# GBZLNDShield.net
KiCad netlist of a schematic drawn in EAGLE
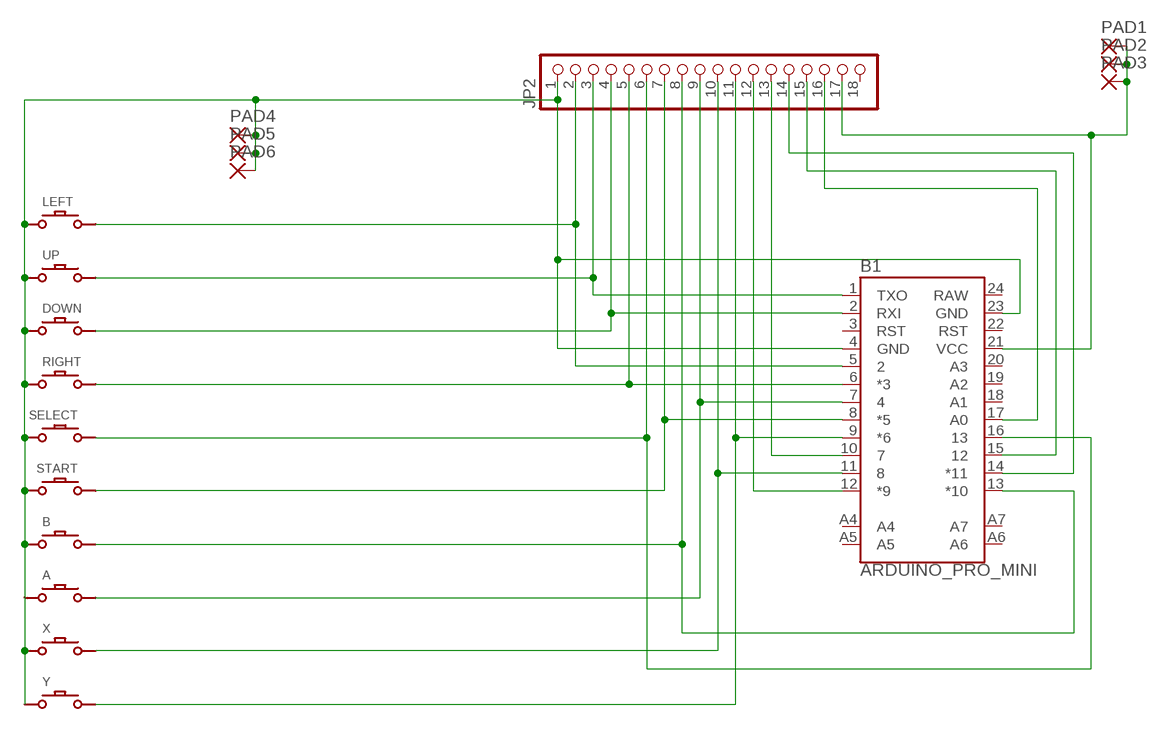
[diagram p0: schematic, sheet 1]

(export (version "E")
  (design (tool "Eeschema 10.0.6"))
  (components
    (comp (ref "A")
      (value "DMG-BTN")
      (footprint "eagle-import:DMG-BTN")
      (libsource (lib "eagle-import") (part "DMG-BTNREGULAR"))
    )
    (comp (ref "B")
      (value "DMG-BTN")
      (footprint "eagle-import:DMG-BTN")
      (libsource (lib "eagle-import") (part "DMG-BTNREGULAR"))
    )
    (comp (ref "B1")
      (value "ARDUINO_PRO_MINI")
      (footprint "eagle-import:ARDUINO_PRO_MINI")
      (libsource (lib "eagle-import") (part "ARDUINO_PRO_MINI"))
    )
    (comp (ref "DOWN")
      (value "DMG-BTN")
      (footprint "eagle-import:DMG-BTN")
      (libsource (lib "eagle-import") (part "DMG-BTNREGULAR"))
    )
    (comp (ref "JP2")
      (value "PINHD-1X18-BIG")
      (footprint "eagle-import:1X18-BIG")
      (libsource (lib "eagle-import") (part "PINHD-1X18-BIG"))
    )
    (comp (ref "LEFT")
      (value "DMG-BTN")
      (footprint "eagle-import:DMG-BTN")
      (libsource (lib "eagle-import") (part "DMG-BTNREGULAR"))
    )
    (comp (ref "PAD1")
      (value "SMD5")
      (footprint "eagle-import:SMD2,54-5,08")
      (libsource (lib "eagle-import") (part "SMD5"))
    )
    (comp (ref "PAD2")
      (value "SMD5")
      (footprint "eagle-import:SMD2,54-5,08")
      (libsource (lib "eagle-import") (part "SMD5"))
    )
    (comp (ref "PAD3")
      (value "SMD5")
      (footprint "eagle-import:SMD2,54-5,08")
      (libsource (lib "eagle-import") (part "SMD5"))
    )
    (comp (ref "PAD4")
      (value "SMD5")
      (footprint "eagle-import:SMD2,54-5,08")
      (libsource (lib "eagle-import") (part "SMD5"))
    )
    (comp (ref "PAD5")
      (value "SMD5")
      (footprint "eagle-import:SMD2,54-5,08")
      (libsource (lib "eagle-import") (part "SMD5"))
    )
    (comp (ref "PAD6")
      (value "SMD5")
      (footprint "eagle-import:SMD2,54-5,08")
      (libsource (lib "eagle-import") (part "SMD5"))
    )
    (comp (ref "RIGHT")
      (value "DMG-BTN")
      (footprint "eagle-import:DMG-BTN")
      (libsource (lib "eagle-import") (part "DMG-BTNREGULAR"))
    )
    (comp (ref "SELECT")
      (value "DMG-BTN")
      (footprint "eagle-import:DMG-SEL")
      (libsource (lib "eagle-import") (part "DMG-BTNSELECT"))
    )
    (comp (ref "START")
      (value "DMG-BTN")
      (footprint "eagle-import:DMG-SEL")
      (libsource (lib "eagle-import") (part "DMG-BTNSELECT"))
    )
    (comp (ref "UP")
      (value "DMG-BTN")
      (footprint "eagle-import:DMG-BTN")
      (libsource (lib "eagle-import") (part "DMG-BTNREGULAR"))
    )
    (comp (ref "X")
      (value "DMG-BTN")
      (footprint "eagle-import:DMG-BTN")
      (libsource (lib "eagle-import") (part "DMG-BTNREGULAR"))
    )
    (comp (ref "Y")
      (value "DMG-BTN")
      (footprint "eagle-import:DMG-BTN")
      (libsource (lib "eagle-import") (part "DMG-BTNREGULAR"))
    )
  )
  (nets
    (net (code "1") (name "/RAW") (class "Default")
      (node (ref "B1") (pin "24") (pinfunction "RAW_24") (pintype "power_in"))
    )
    (net (code "2") (name "Net-(B1-*3)") (class "Default")
      (node (ref "B1") (pin "6") (pinfunction "*3_6") (pintype "bidirectional"))
      (node (ref "JP2") (pin "5") (pinfunction "5_5") (pintype "passive"))
      (node (ref "RIGHT") (pin "P$2") (pinfunction "P$2_P$2") (pintype "bidirectional"))
    )
    (net (code "3") (name "Net-(B1-*5)") (class "Default")
      (node (ref "B1") (pin "8") (pinfunction "*5_8") (pintype "bidirectional"))
      (node (ref "JP2") (pin "7") (pinfunction "7_7") (pintype "passive"))
      (node (ref "START") (pin "P$1") (pinfunction "P$1_P$1") (pintype "bidirectional"))
    )
    (net (code "4") (name "Net-(B1-*6)") (class "Default")
      (node (ref "B1") (pin "9") (pinfunction "*6_9") (pintype "bidirectional"))
      (node (ref "JP2") (pin "11") (pinfunction "11_11") (pintype "passive"))
      (node (ref "Y") (pin "P$2") (pinfunction "P$2_P$2") (pintype "bidirectional"))
    )
    (net (code "5") (name "Net-(B1-*9)") (class "Default")
      (node (ref "B1") (pin "12") (pinfunction "*9_12") (pintype "bidirectional"))
      (node (ref "JP2") (pin "12") (pinfunction "12_12") (pintype "passive"))
    )
    (net (code "6") (name "Net-(B1-*10)") (class "Default")
      (node (ref "B") (pin "P$2") (pinfunction "P$2_P$2") (pintype "bidirectional"))
      (node (ref "B1") (pin "13") (pinfunction "*10_13") (pintype "bidirectional"))
      (node (ref "JP2") (pin "8") (pinfunction "8_8") (pintype "passive"))
    )
    (net (code "7") (name "Net-(B1-*11)") (class "Default")
      (node (ref "B1") (pin "14") (pinfunction "*11_14") (pintype "bidirectional"))
      (node (ref "JP2") (pin "14") (pinfunction "14_14") (pintype "passive"))
    )
    (net (code "8") (name "Net-(B1-2)") (class "Default")
      (node (ref "B1") (pin "5") (pinfunction "2_5") (pintype "bidirectional"))
      (node (ref "JP2") (pin "2") (pinfunction "2_2") (pintype "passive"))
      (node (ref "LEFT") (pin "P$2") (pinfunction "P$2_P$2") (pintype "bidirectional"))
    )
    (net (code "9") (name "Net-(B1-4)") (class "Default")
      (node (ref "A") (pin "P$2") (pinfunction "P$2_P$2") (pintype "bidirectional"))
      (node (ref "B1") (pin "7") (pinfunction "4_7") (pintype "bidirectional"))
      (node (ref "JP2") (pin "9") (pinfunction "9_9") (pintype "passive"))
    )
    (net (code "10") (name "Net-(B1-7)") (class "Default")
      (node (ref "B1") (pin "10") (pinfunction "7_10") (pintype "bidirectional"))
      (node (ref "JP2") (pin "13") (pinfunction "13_13") (pintype "passive"))
    )
    (net (code "11") (name "Net-(B1-8)") (class "Default")
      (node (ref "B1") (pin "11") (pinfunction "8_11") (pintype "bidirectional"))
      (node (ref "JP2") (pin "10") (pinfunction "10_10") (pintype "passive"))
      (node (ref "X") (pin "P$2") (pinfunction "P$2_P$2") (pintype "bidirectional"))
    )
    (net (code "12") (name "Net-(B1-12)") (class "Default")
      (node (ref "B1") (pin "15") (pinfunction "12_15") (pintype "bidirectional"))
      (node (ref "JP2") (pin "15") (pinfunction "15_15") (pintype "passive"))
    )
    (net (code "13") (name "Net-(B1-13)") (class "Default")
      (node (ref "B1") (pin "16") (pinfunction "13_16") (pintype "bidirectional"))
      (node (ref "JP2") (pin "6") (pinfunction "6_6") (pintype "passive"))
      (node (ref "SELECT") (pin "P$1") (pinfunction "P$1_P$1") (pintype "bidirectional"))
    )
    (net (code "14") (name "Net-(B1-A0)") (class "Default")
      (node (ref "B1") (pin "17") (pinfunction "A0_17") (pintype "bidirectional"))
      (node (ref "JP2") (pin "16") (pinfunction "16_16") (pintype "passive"))
    )
    (net (code "15") (name "Net-(B1-RXI)") (class "Default")
      (node (ref "B1") (pin "2") (pinfunction "RXI_2") (pintype "bidirectional"))
      (node (ref "DOWN") (pin "P$2") (pinfunction "P$2_P$2") (pintype "bidirectional"))
      (node (ref "JP2") (pin "4") (pinfunction "4_4") (pintype "passive"))
    )
    (net (code "16") (name "Net-(B1-TXO)") (class "Default")
      (node (ref "B1") (pin "1") (pinfunction "TXO_1") (pintype "bidirectional"))
      (node (ref "JP2") (pin "3") (pinfunction "3_3") (pintype "passive"))
      (node (ref "UP") (pin "P$2") (pinfunction "P$2_P$2") (pintype "bidirectional"))
    )
    (net (code "17") (name "Net-(B1-VCC)") (class "Default")
      (node (ref "B1") (pin "21") (pinfunction "VCC_21") (pintype "power_in"))
      (node (ref "JP2") (pin "17") (pinfunction "17_17") (pintype "passive"))
      (node (ref "PAD1") (pin "1") (pinfunction "P_1") (pintype "passive"))
      (node (ref "PAD2") (pin "1") (pinfunction "P_1") (pintype "passive"))
      (node (ref "PAD3") (pin "1") (pinfunction "P_1") (pintype "passive"))
    )
    (net (code "18") (name "Net-(PAD4-P)") (class "Default")
      (node (ref "A") (pin "P$1") (pinfunction "P$1_P$1") (pintype "bidirectional"))
      (node (ref "B") (pin "P$1") (pinfunction "P$1_P$1") (pintype "bidirectional"))
      (node (ref "B1") (pin "23") (pinfunction "GND_23") (pintype "power_in"))
      (node (ref "B1") (pin "4") (pinfunction "GND_4") (pintype "power_in"))
      (node (ref "DOWN") (pin "P$1") (pinfunction "P$1_P$1") (pintype "bidirectional"))
      (node (ref "JP2") (pin "1") (pinfunction "1_1") (pintype "passive"))
      (node (ref "LEFT") (pin "P$1") (pinfunction "P$1_P$1") (pintype "bidirectional"))
      (node (ref "PAD4") (pin "1") (pinfunction "P_1") (pintype "passive"))
      (node (ref "PAD5") (pin "1") (pinfunction "P_1") (pintype "passive"))
      (node (ref "PAD6") (pin "1") (pinfunction "P_1") (pintype "passive"))
      (node (ref "RIGHT") (pin "P$1") (pinfunction "P$1_P$1") (pintype "bidirectional"))
      (node (ref "SELECT") (pin "P$2") (pinfunction "P$2_P$2") (pintype "bidirectional"))
      (node (ref "START") (pin "P$2") (pinfunction "P$2_P$2") (pintype "bidirectional"))
      (node (ref "UP") (pin "P$1") (pinfunction "P$1_P$1") (pintype "bidirectional"))
      (node (ref "X") (pin "P$1") (pinfunction "P$1_P$1") (pintype "bidirectional"))
      (node (ref "Y") (pin "P$1") (pinfunction "P$1_P$1") (pintype "bidirectional"))
    )
    (net (code "19") (name "unconnected-(B1-A1-Pad18)") (class "Default")
      (node (ref "B1") (pin "18") (pinfunction "A1_18") (pintype "bidirectional"))
    )
    (net (code "20") (name "unconnected-(B1-A2-Pad19)") (class "Default")
      (node (ref "B1") (pin "19") (pinfunction "A2_19") (pintype "bidirectional"))
    )
    (net (code "21") (name "unconnected-(B1-A3-Pad20)") (class "Default")
      (node (ref "B1") (pin "20") (pinfunction "A3_20") (pintype "bidirectional"))
    )
    (net (code "22") (name "unconnected-(B1-PadA4)") (class "Default")
      (node (ref "B1") (pin "A4") (pinfunction "A4_A4") (pintype "bidirectional"))
    )
    (net (code "23") (name "unconnected-(B1-PadA5)") (class "Default")
      (node (ref "B1") (pin "A5") (pinfunction "A5_A5") (pintype "bidirectional"))
    )
    (net (code "24") (name "unconnected-(B1-PadA6)") (class "Default")
      (node (ref "B1") (pin "A6") (pinfunction "A6_A6") (pintype "bidirectional"))
    )
    (net (code "25") (name "unconnected-(B1-PadA7)") (class "Default")
      (node (ref "B1") (pin "A7") (pinfunction "A7_A7") (pintype "bidirectional"))
    )
    (net (code "26") (name "unconnected-(B1-RST-Pad3)") (class "Default")
      (node (ref "B1") (pin "3") (pinfunction "RST_3") (pintype "bidirectional"))
    )
    (net (code "27") (name "unconnected-(B1-RST-Pad22)") (class "Default")
      (node (ref "B1") (pin "22") (pinfunction "RST_22") (pintype "bidirectional"))
    )
    (net (code "28") (name "unconnected-(JP2-Pad18)") (class "Default")
      (node (ref "JP2") (pin "18") (pinfunction "18_18") (pintype "passive"))
    )
  )
)
